# CAN_transciever.net
KiCad netlist of a schematic drawn in Altium Designer
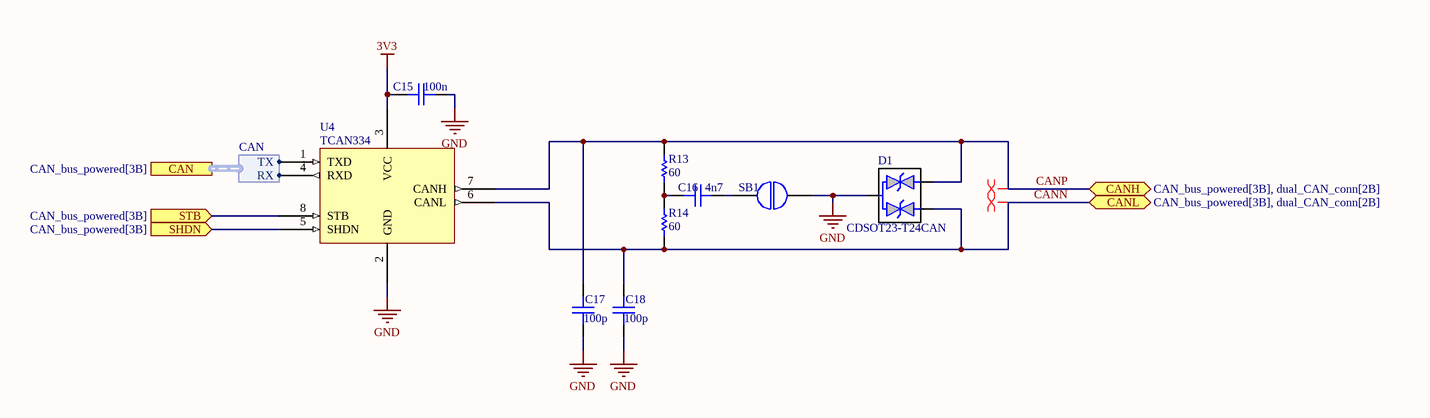
[diagram p0: CAN_transciever.SchDoc]

(export (version "E")
  (design (tool "Eeschema 10.0.6"))
  (components
    (comp (ref "C15")
      (value "100n")
      (description "Capacitor")
      (libsource (lib "drfc_schlib") (part "Capacitor"))
    )
    (comp (ref "C16")
      (value "4n7")
      (description "Capacitor")
      (libsource (lib "drfc_schlib") (part "Capacitor"))
    )
    (comp (ref "C17")
      (value "100p")
      (description "Capacitor")
      (libsource (lib "drfc_schlib") (part "Capacitor"))
    )
    (comp (ref "C18")
      (value "100p")
      (description "Capacitor")
      (libsource (lib "drfc_schlib") (part "Capacitor"))
    )
    (comp (ref "D1") (value "CDSOT23-T24CAN") (libsource (lib "drfc_schlib") (part "Dual TVS Diode")))
    (comp (ref "R13") (value "60") (description "Resistor") (libsource (lib "drfc_schlib") (part "Resistor")))
    (comp (ref "R14") (value "60") (description "Resistor") (libsource (lib "drfc_schlib") (part "Resistor")))
    (comp (ref "SB1")
      (value "NO Solder Bridge")
      (description "Normally Open Solder Bridge")
      (libsource (lib "drfc_schlib") (part "NO Solder Bridge"))
    )
    (comp (ref "U4")
      (value "TCAN334")
      (description "Can tranciever with shutdown and standby with wake")
      (libsource (lib "drfc_schlib") (part "TCAN334"))
    )
  )
  (nets
    (net (code "2") (name "/CANN") (class "Default")
      (node (ref "C18") (pin "1") (pinfunction "1_1") (pintype "passive"))
      (node (ref "D1") (pin "1") (pinfunction "1_1") (pintype "passive"))
      (node (ref "R14") (pin "2") (pinfunction "2_2") (pintype "passive"))
      (node (ref "U4") (pin "6") (pinfunction "CANL_6") (pintype "output"))
    )
    (net (code "3") (name "/CANP") (class "Default")
      (node (ref "C17") (pin "1") (pinfunction "1_1") (pintype "passive"))
      (node (ref "D1") (pin "2") (pinfunction "2_2") (pintype "passive"))
      (node (ref "R13") (pin "1") (pinfunction "1_1") (pintype "passive"))
      (node (ref "U4") (pin "7") (pinfunction "CANH_7") (pintype "output"))
    )
    (net (code "4") (name "/RX") (class "Default")
      (node (ref "U4") (pin "4") (pinfunction "RXD_4") (pintype "output"))
    )
    (net (code "5") (name "/SHDN") (class "Default")
      (node (ref "U4") (pin "5") (pinfunction "SHDN_5") (pintype "input"))
    )
    (net (code "6") (name "/STB") (class "Default")
      (node (ref "U4") (pin "8") (pinfunction "STB_8") (pintype "input"))
    )
    (net (code "7") (name "/TX") (class "Default")
      (node (ref "U4") (pin "1") (pinfunction "TXD_1") (pintype "input"))
    )
    (net (code "9") (name "3V3") (class "Default")
      (node (ref "C15") (pin "2") (pinfunction "2_2") (pintype "passive"))
      (node (ref "U4") (pin "3") (pinfunction "VCC_3") (pintype "power_in"))
    )
    (net (code "10") (name "GND") (class "Default")
      (node (ref "C15") (pin "1") (pinfunction "1_1") (pintype "passive"))
      (node (ref "C17") (pin "2") (pinfunction "2_2") (pintype "passive"))
      (node (ref "C18") (pin "2") (pinfunction "2_2") (pintype "passive"))
      (node (ref "D1") (pin "3") (pinfunction "3_3") (pintype "passive"))
      (node (ref "SB1") (pin "1") (pinfunction "1_1") (pintype "open_collector"))
      (node (ref "U4") (pin "2") (pinfunction "GND_2") (pintype "power_in"))
    )
    (net (code "11") (name "Net-(C16-Pad1)") (class "Default")
      (node (ref "C16") (pin "1") (pinfunction "1_1") (pintype "passive"))
      (node (ref "SB1") (pin "2") (pinfunction "2_2") (pintype "open_collector"))
    )
    (net (code "12") (name "Net-(C16-Pad2)") (class "Default")
      (node (ref "C16") (pin "2") (pinfunction "2_2") (pintype "passive"))
      (node (ref "R13") (pin "2") (pinfunction "2_2") (pintype "passive"))
      (node (ref "R14") (pin "1") (pinfunction "1_1") (pintype "passive"))
    )
  )
)
